# one_planar_sensor_connector_hall_crossbo.net
KiCad netlist of a schematic drawn in Altium Designer
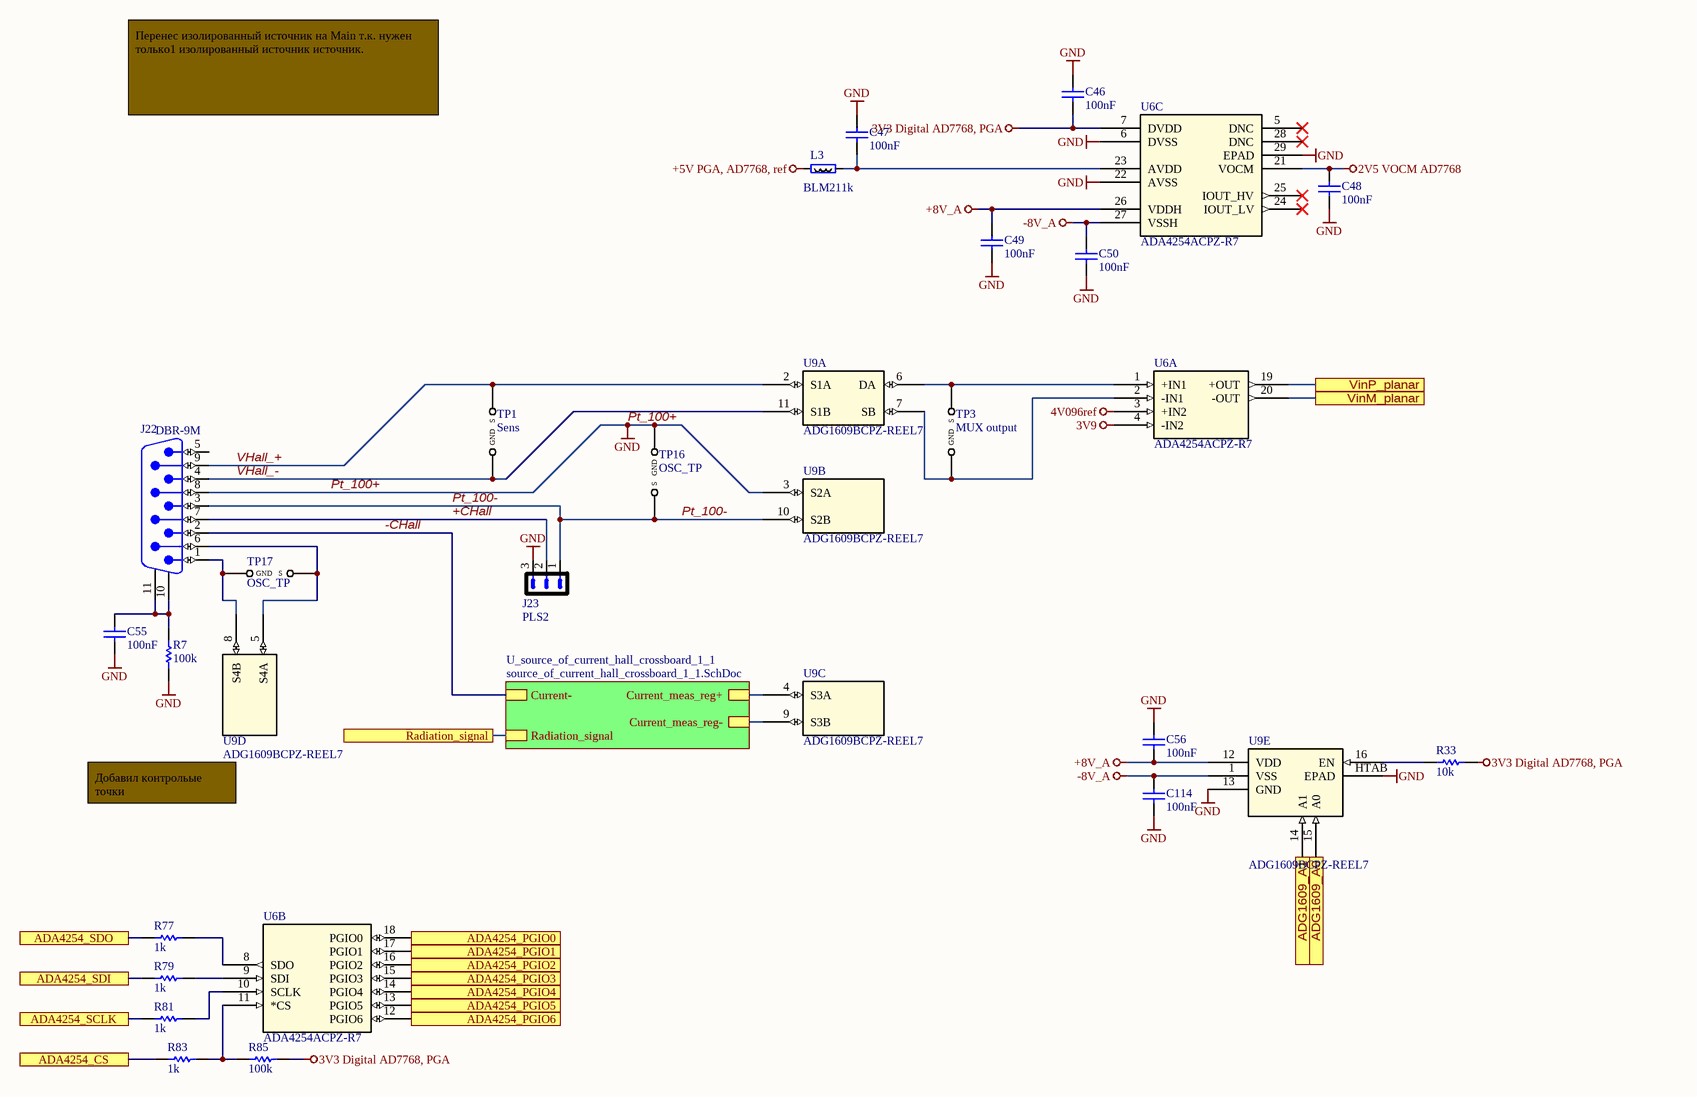
[diagram p0: one_planar_sensor_connector_hall_crossboard_1_1.SchDoc]

(export (version "E")
  (design (tool "Eeschema 10.0.6"))
  (components
    (comp (ref "C46")
      (value "100nF")
      (footprint "hall_crossboard_1_1_library:0603C")
      (description "Capacitor 0402 / 0603 / 0805")
      (libsource (lib "hall_crossboard_1_1_library") (part "Capacitor_ST"))
    )
    (comp (ref "C47")
      (value "100nF")
      (footprint "hall_crossboard_1_1_library:0603C")
      (description "Capacitor 0402 / 0603 / 0805")
      (libsource (lib "hall_crossboard_1_1_library") (part "Capacitor_ST"))
    )
    (comp (ref "C48")
      (value "100nF")
      (footprint "hall_crossboard_1_1_library:0603C")
      (description "Capacitor 0402 / 0603 / 0805")
      (libsource (lib "hall_crossboard_1_1_library") (part "Capacitor_ST"))
    )
    (comp (ref "C49")
      (value "100nF")
      (footprint "hall_crossboard_1_1_library:0603C")
      (description "Capacitor 0402 / 0603 / 0805")
      (libsource (lib "hall_crossboard_1_1_library") (part "Capacitor_ST"))
    )
    (comp (ref "C50")
      (value "100nF")
      (footprint "hall_crossboard_1_1_library:0603C")
      (description "Capacitor 0402 / 0603 / 0805")
      (libsource (lib "hall_crossboard_1_1_library") (part "Capacitor_ST"))
    )
    (comp (ref "C55")
      (value "100nF")
      (footprint "hall_crossboard_1_1_library:0603C")
      (description "Capacitor 0402 / 0603 / 0805")
      (libsource (lib "hall_crossboard_1_1_library") (part "Capacitor_ST"))
    )
    (comp (ref "C56")
      (value "100nF")
      (footprint "hall_crossboard_1_1_library:0603C")
      (description "Capacitor 0402 / 0603 / 0805")
      (libsource (lib "hall_crossboard_1_1_library") (part "Capacitor_ST"))
    )
    (comp (ref "C114")
      (value "100nF")
      (footprint "hall_crossboard_1_1_library:0603C")
      (description "Capacitor 0402 / 0603 / 0805")
      (libsource (lib "hall_crossboard_1_1_library") (part "Capacitor_ST"))
    )
    (comp (ref "J22")
      (value "DBR-9M")
      (footprint "footprint_hall_crossboard_1_1_library:AMPHENOL_L717DFE09P1ATN")
      (description "Вилка  DSUB 9 угловая")
      (libsource (lib "schematic_hall_crossboard_1_1_library") (part "D_SUB_9M"))
    )
    (comp (ref "J23")
      (value "PLS2")
      (footprint "COMATEL_385.0358.1.03.400")
      (description "PLS3")
      (libsource (lib "hall_crossboard_1_1_library") (part "PLS3"))
    )
    (comp (ref "L3")
      (value "BLM211k")
      (footprint "footprint_hall_crossboard_1_1_library:RESC2012X50N")
      (description "SMD Ferrite bead 0805")
      (libsource (lib "schematic_hall_crossboard_1_1_library") (part "BLM21"))
    )
    (comp (ref "R7")
      (value "100k")
      (footprint "0603R")
      (description "Resistor 0402 / 0603 / 0805")
      (libsource (lib "hall_crossboard_1_1_library") (part "Resistor_ST"))
    )
    (comp (ref "R33")
      (value "10k")
      (footprint "0603R")
      (description "Resistor 0402 / 0603 / 0805")
      (libsource (lib "hall_crossboard_1_1_library") (part "Resistor_ST"))
    )
    (comp (ref "R77")
      (value "1k")
      (footprint "0603R")
      (description "Resistor 0402 / 0603 / 0805")
      (libsource (lib "hall_crossboard_1_1_library") (part "Resistor_ST"))
    )
    (comp (ref "R79")
      (value "1k")
      (footprint "0603R")
      (description "Resistor 0402 / 0603 / 0805")
      (libsource (lib "hall_crossboard_1_1_library") (part "Resistor_ST"))
    )
    (comp (ref "R81")
      (value "1k")
      (footprint "0603R")
      (description "Resistor 0402 / 0603 / 0805")
      (libsource (lib "hall_crossboard_1_1_library") (part "Resistor_ST"))
    )
    (comp (ref "R83")
      (value "1k")
      (footprint "0603R")
      (description "Resistor 0402 / 0603 / 0805")
      (libsource (lib "hall_crossboard_1_1_library") (part "Resistor_ST"))
    )
    (comp (ref "R85")
      (value "100k")
      (footprint "0603R")
      (description "Resistor 0402 / 0603 / 0805")
      (libsource (lib "hall_crossboard_1_1_library") (part "Resistor_ST"))
    )
    (comp (ref "TP1")
      (value "Sens")
      (footprint "TP2")
      (description "Контрольная точка для подключения осциллографа короткой землёй")
      (libsource (lib "hall_crossboard_1_1_library") (part "OscTP"))
    )
    (comp (ref "TP3")
      (value "MUX output")
      (footprint "TP2")
      (description "Контрольная точка для подключения осциллографа короткой землёй")
      (libsource (lib "hall_crossboard_1_1_library") (part "OscTP"))
    )
    (comp (ref "TP16")
      (value "OSC_TP")
      (footprint "TP2")
      (description "Контрольная точка для подключения осциллографа короткой землёй")
      (libsource (lib "hall_crossboard_1_1_library") (part "OscTP"))
    )
    (comp (ref "TP17")
      (value "OSC_TP")
      (footprint "TP2")
      (description "Контрольная точка для подключения осциллографа короткой землёй")
      (libsource (lib "hall_crossboard_1_1_library") (part "OscTP"))
    )
    (comp (ref "U6")
      (value "ADA4254ACPZ-R7")
      (footprint "footprint_hall_crossboard_1_1_library:CP-28-10_ADI-M")
      (description "No Description Available")
      (libsource (lib "schematic_hall_crossboard_1_1_library") (part "ADA4254ACPZ-R7"))
    )
    (comp (ref "U9")
      (value "ADG1609BCPZ-REEL7")
      (footprint "footprint_hall_crossboard_1_1_library:CP_16_22_ADI-M")
      (description "No Description Available")
      (libsource (lib "") (part "ADG1609BCPZ-REEL7_1"))
    )
  )
  (nets
    (net (code "1") (name "+5V PGA, AD7768, ref") (class "Default")
      (node (ref "L3") (pin "1") (pinfunction "1_1") (pintype "passive"))
    )
    (net (code "2") (name "+8V_A") (class "Default")
      (node (ref "C49") (pin "2") (pinfunction "2_2") (pintype "passive"))
      (node (ref "C56") (pin "1") (pinfunction "1_1") (pintype "passive"))
      (node (ref "U6") (pin "26") (pinfunction "VDDH_26") (pintype "power_in"))
      (node (ref "U9") (pin "12") (pinfunction "VDD_12") (pintype "power_in"))
    )
    (net (code "3") (name "-8V_A") (class "Default")
      (node (ref "C114") (pin "2") (pinfunction "2_2") (pintype "passive"))
      (node (ref "C50") (pin "2") (pinfunction "2_2") (pintype "passive"))
      (node (ref "U6") (pin "27") (pinfunction "VSSH_27") (pintype "power_in"))
      (node (ref "U9") (pin "1") (pinfunction "VSS_1") (pintype "power_in"))
    )
    (net (code "4") (name "/+CHall") (class "Default")
      (node (ref "J22") (pin "7") (pinfunction "7_7") (pintype "bidirectional"))
      (node (ref "J23") (pin "2") (pinfunction "2_2") (pintype "bidirectional"))
    )
    (net (code "5") (name "/-CHall") (class "Default")
      (node (ref "J22") (pin "2") (pinfunction "2_2") (pintype "bidirectional"))
    )
    (net (code "6") (name "/ADA4254_CS") (class "Default")
      (node (ref "R83") (pin "1") (pinfunction "1_1") (pintype "passive"))
    )
    (net (code "7") (name "/ADA4254_PGIO0") (class "Default")
      (node (ref "U6") (pin "18") (pinfunction "PGIO0_18") (pintype "bidirectional"))
    )
    (net (code "8") (name "/ADA4254_PGIO1") (class "Default")
      (node (ref "U6") (pin "17") (pinfunction "PGIO1_17") (pintype "bidirectional"))
    )
    (net (code "9") (name "/ADA4254_PGIO2") (class "Default")
      (node (ref "U6") (pin "16") (pinfunction "PGIO2_16") (pintype "bidirectional"))
    )
    (net (code "10") (name "/ADA4254_PGIO3") (class "Default")
      (node (ref "U6") (pin "15") (pinfunction "PGIO3_15") (pintype "bidirectional"))
    )
    (net (code "11") (name "/ADA4254_PGIO4") (class "Default")
      (node (ref "U6") (pin "14") (pinfunction "PGIO4_14") (pintype "bidirectional"))
    )
    (net (code "12") (name "/ADA4254_PGIO5") (class "Default")
      (node (ref "U6") (pin "13") (pinfunction "PGIO5_13") (pintype "bidirectional"))
    )
    (net (code "13") (name "/ADA4254_PGIO6") (class "Default")
      (node (ref "U6") (pin "12") (pinfunction "PGIO6_12") (pintype "bidirectional"))
    )
    (net (code "14") (name "/ADA4254_SCLK") (class "Default")
      (node (ref "R81") (pin "1") (pinfunction "1_1") (pintype "passive"))
    )
    (net (code "15") (name "/ADA4254_SDI") (class "Default")
      (node (ref "R79") (pin "1") (pinfunction "1_1") (pintype "passive"))
    )
    (net (code "16") (name "/ADA4254_SDO") (class "Default")
      (node (ref "R77") (pin "1") (pinfunction "1_1") (pintype "passive"))
    )
    (net (code "17") (name "/ADG1609_A0") (class "Default")
      (node (ref "U9") (pin "15") (pinfunction "A0_15") (pintype "input"))
    )
    (net (code "18") (name "/ADG1609_A1") (class "Default")
      (node (ref "U9") (pin "14") (pinfunction "A1_14") (pintype "input"))
    )
    (net (code "19") (name "/Current_meas_reg+") (class "Default")
      (node (ref "U9") (pin "4") (pinfunction "S3A_4") (pintype "bidirectional"))
    )
    (net (code "20") (name "/Current_meas_reg-") (class "Default")
      (node (ref "U9") (pin "9") (pinfunction "S3B_9") (pintype "bidirectional"))
    )
    (net (code "21") (name "/Pt_100-") (class "Default")
      (node (ref "J22") (pin "3") (pinfunction "3_3") (pintype "bidirectional"))
      (node (ref "J23") (pin "1") (pinfunction "1_1") (pintype "bidirectional"))
      (node (ref "TP16") (pin "1") (pinfunction "S_1") (pintype "passive"))
      (node (ref "U9") (pin "10") (pinfunction "S2B_10") (pintype "bidirectional"))
    )
    (net (code "23") (name "/VHall_+") (class "Default")
      (node (ref "J22") (pin "9") (pinfunction "9_9") (pintype "bidirectional"))
      (node (ref "TP1") (pin "1") (pinfunction "S_1") (pintype "passive"))
      (node (ref "U9") (pin "2") (pinfunction "S1A_2") (pintype "bidirectional"))
    )
    (net (code "24") (name "/VHall_-") (class "Default")
      (node (ref "J22") (pin "4") (pinfunction "4_4") (pintype "bidirectional"))
      (node (ref "TP1") (pin "2") (pinfunction "GND_2") (pintype "passive"))
      (node (ref "U9") (pin "11") (pinfunction "S1B_11") (pintype "bidirectional"))
    )
    (net (code "25") (name "/VinM_planar") (class "Default")
      (node (ref "U6") (pin "20") (pinfunction "-OUT_20") (pintype "output"))
    )
    (net (code "26") (name "/VinP_planar") (class "Default")
      (node (ref "U6") (pin "19") (pinfunction "+OUT_19") (pintype "output"))
    )
    (net (code "27") (name "2V5 VOCM AD7768") (class "Default")
      (node (ref "C48") (pin "2") (pinfunction "2_2") (pintype "passive"))
      (node (ref "U6") (pin "21") (pinfunction "VOCM_21") (pintype "power_in"))
    )
    (net (code "28") (name "3V3 Digital AD7768, PGA") (class "Default")
      (node (ref "C46") (pin "1") (pinfunction "1_1") (pintype "passive"))
      (node (ref "R85") (pin "2") (pinfunction "2_2") (pintype "passive"))
      (node (ref "U6") (pin "7") (pinfunction "DVDD_7") (pintype "power_in"))
    )
    (net (code "29") (name "3V9") (class "Default")
      (node (ref "U6") (pin "4") (pinfunction "-IN2_4") (pintype "input"))
    )
    (net (code "30") (name "4V096ref") (class "Default")
      (node (ref "U6") (pin "3") (pinfunction "+IN2_3") (pintype "input"))
    )
    (net (code "31") (name "GND") (class "Default")
      (node (ref "C114") (pin "1") (pinfunction "1_1") (pintype "passive"))
      (node (ref "C46") (pin "2") (pinfunction "2_2") (pintype "passive"))
      (node (ref "C47") (pin "1") (pinfunction "1_1") (pintype "passive"))
      (node (ref "C48") (pin "1") (pinfunction "1_1") (pintype "passive"))
      (node (ref "C49") (pin "1") (pinfunction "1_1") (pintype "passive"))
      (node (ref "C50") (pin "1") (pinfunction "1_1") (pintype "passive"))
      (node (ref "C55") (pin "1") (pinfunction "1_1") (pintype "passive"))
      (node (ref "C56") (pin "2") (pinfunction "2_2") (pintype "passive"))
      (node (ref "J22") (pin "8") (pinfunction "8_8") (pintype "bidirectional"))
      (node (ref "J23") (pin "3") (pinfunction "3_3") (pintype "bidirectional"))
      (node (ref "R7") (pin "1") (pinfunction "1_1") (pintype "passive"))
      (node (ref "TP16") (pin "2") (pinfunction "GND_2") (pintype "passive"))
      (node (ref "U6") (pin "22") (pinfunction "AVSS_22") (pintype "power_in"))
      (node (ref "U6") (pin "29") (pinfunction "EPAD_29") (pintype "power_in"))
      (node (ref "U6") (pin "6") (pinfunction "DVSS_6") (pintype "power_in"))
      (node (ref "U9") (pin "13") (pinfunction "GND_13") (pintype "power_in"))
      (node (ref "U9") (pin "3") (pinfunction "S2A_3") (pintype "bidirectional"))
      (node (ref "U9") (pin "HTAB") (pinfunction "EPAD_HTAB") (pintype "passive"))
    )
    (net (code "32") (name "Net-(C55-Pad2)") (class "Default")
      (node (ref "C55") (pin "2") (pinfunction "2_2") (pintype "passive"))
      (node (ref "J22") (pin "10") (pinfunction "10_10") (pintype "passive"))
      (node (ref "J22") (pin "11") (pinfunction "11_11") (pintype "passive"))
      (node (ref "R7") (pin "2") (pinfunction "2_2") (pintype "passive"))
    )
    (net (code "33") (name "Net-(TP3-GND)") (class "Default")
      (node (ref "TP3") (pin "2") (pinfunction "GND_2") (pintype "passive"))
      (node (ref "U6") (pin "2") (pinfunction "-IN1_2") (pintype "input"))
      (node (ref "U9") (pin "7") (pinfunction "SB_7") (pintype "bidirectional"))
    )
    (net (code "34") (name "Net-(TP3-S)") (class "Default")
      (node (ref "TP3") (pin "1") (pinfunction "S_1") (pintype "passive"))
      (node (ref "U6") (pin "1") (pinfunction "+IN1_1") (pintype "input"))
      (node (ref "U9") (pin "6") (pinfunction "DA_6") (pintype "bidirectional"))
    )
    (net (code "35") (name "Net-(TP17-GND)") (class "Default")
      (node (ref "J22") (pin "1") (pinfunction "1_1") (pintype "bidirectional"))
      (node (ref "TP17") (pin "2") (pinfunction "GND_2") (pintype "passive"))
      (node (ref "U9") (pin "8") (pinfunction "S4B_8") (pintype "bidirectional"))
    )
    (net (code "36") (name "Net-(TP17-S)") (class "Default")
      (node (ref "J22") (pin "6") (pinfunction "6_6") (pintype "bidirectional"))
      (node (ref "TP17") (pin "1") (pinfunction "S_1") (pintype "passive"))
      (node (ref "U9") (pin "5") (pinfunction "S4A_5") (pintype "bidirectional"))
    )
    (net (code "37") (name "Net-(U6B-*CS)") (class "Default")
      (node (ref "R83") (pin "2") (pinfunction "2_2") (pintype "passive"))
      (node (ref "R85") (pin "1") (pinfunction "1_1") (pintype "passive"))
      (node (ref "U6") (pin "11") (pinfunction "*CS_11") (pintype "input"))
    )
    (net (code "38") (name "Net-(U6B-SCLK)") (class "Default")
      (node (ref "R81") (pin "2") (pinfunction "2_2") (pintype "passive"))
      (node (ref "U6") (pin "10") (pinfunction "SCLK_10") (pintype "input"))
    )
    (net (code "39") (name "Net-(U6B-SDI)") (class "Default")
      (node (ref "R79") (pin "2") (pinfunction "2_2") (pintype "passive"))
      (node (ref "U6") (pin "9") (pinfunction "SDI_9") (pintype "input"))
    )
    (net (code "40") (name "Net-(U6B-SDO)") (class "Default")
      (node (ref "R77") (pin "2") (pinfunction "2_2") (pintype "passive"))
      (node (ref "U6") (pin "8") (pinfunction "SDO_8") (pintype "output"))
    )
    (net (code "41") (name "Net-(U6C-AVDD)") (class "Default")
      (node (ref "C47") (pin "2") (pinfunction "2_2") (pintype "passive"))
      (node (ref "L3") (pin "2") (pinfunction "2_2") (pintype "passive"))
      (node (ref "U6") (pin "23") (pinfunction "AVDD_23") (pintype "power_in"))
    )
    (net (code "42") (name "Net-(U9E-EN)") (class "Default")
      (node (ref "R33") (pin "1") (pinfunction "1_1") (pintype "passive"))
      (node (ref "U9") (pin "16") (pinfunction "EN_16") (pintype "input"))
    )
    (net (code "43") (name "unconnected-(J22-Pad5)") (class "Default")
      (node (ref "J22") (pin "5") (pinfunction "5_5") (pintype "bidirectional"))
    )
    (net (code "44") (name "unconnected-(R33-Pad2)") (class "Default")
      (node (ref "R33") (pin "2") (pinfunction "2_2") (pintype "passive"))
    )
    (net (code "45") (name "unconnected-(U6C-DNC-Pad5)") (class "Default")
      (node (ref "U6") (pin "5") (pinfunction "DNC_5") (pintype "passive+no_connect"))
    )
    (net (code "46") (name "unconnected-(U6C-DNC-Pad28)") (class "Default")
      (node (ref "U6") (pin "28") (pinfunction "DNC_28") (pintype "passive+no_connect"))
    )
    (net (code "47") (name "unconnected-(U6C-IOUT_HV-Pad25)") (class "Default")
      (node (ref "U6") (pin "25") (pinfunction "IOUT_HV_25") (pintype "output+no_connect"))
    )
    (net (code "48") (name "unconnected-(U6C-IOUT_LV-Pad24)") (class "Default")
      (node (ref "U6") (pin "24") (pinfunction "IOUT_LV_24") (pintype "output+no_connect"))
    )
  )
)
